# croc.net
KiCad netlist of a schematic drawn in EAGLE
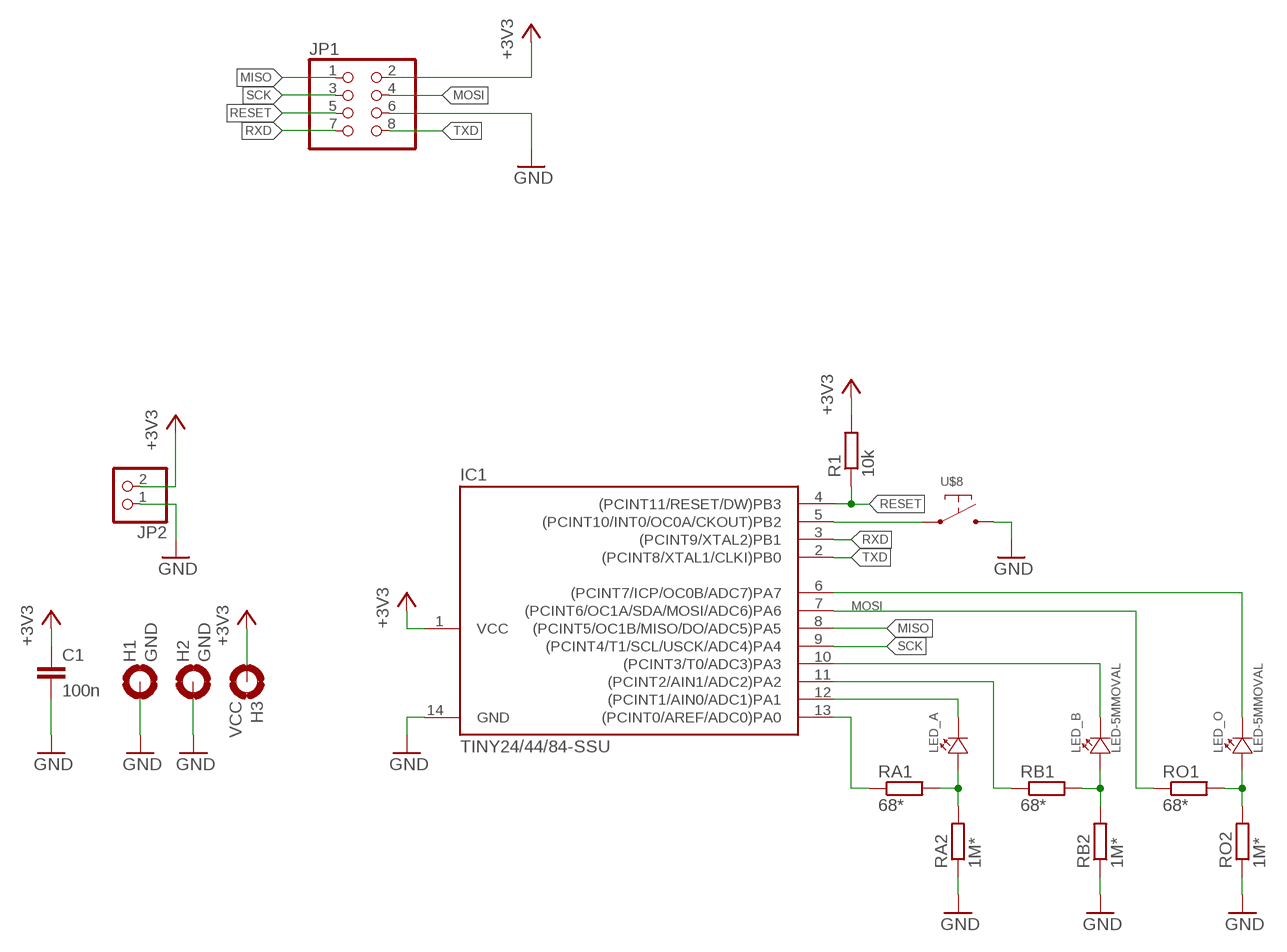
[diagram p0: schematic, sheet 1]

(export (version "E")
  (design (tool "Eeschema 10.0.6"))
  (components
    (comp (ref "C1")
      (value "100n")
      (footprint "eagle-import:C0603")
      (libsource (lib "eagle-import") (part "C-EUC0603"))
    )
    (comp (ref "H1")
      (value "GND")
      (footprint "eagle-import:3,0-PAD")
      (libsource (lib "eagle-import") (part "MOUNT-PAD-ROUND3.0"))
    )
    (comp (ref "H2")
      (value "GND")
      (footprint "eagle-import:3,0-PAD")
      (libsource (lib "eagle-import") (part "MOUNT-PAD-ROUND3.0"))
    )
    (comp (ref "H3")
      (value "VCC")
      (footprint "eagle-import:3,0-PAD")
      (libsource (lib "eagle-import") (part "MOUNT-PAD-ROUND3.0"))
    )
    (comp (ref "IC1")
      (value "TINY24/44/84-SSU")
      (footprint "eagle-import:SOIC14")
      (libsource (lib "eagle-import") (part "TINY24/44/84-SSU"))
    )
    (comp (ref "JP1")
      (value "PINHD-2X4/EDGE")
      (footprint "eagle-import:2X04_EDGE")
      (libsource (lib "eagle-import") (part "PINHD-2X4/EDGE"))
    )
    (comp (ref "JP2")
      (value "PINHD-1X2")
      (footprint "eagle-import:1X02")
      (libsource (lib "eagle-import") (part "PINHD-1X2"))
    )
    (comp (ref "LED_A")
      (value "LED-5MMOVAL")
      (footprint "eagle-import:LED-5MM-EDGE-OVAL")
      (libsource (lib "eagle-import") (part "LED-5MMOVAL"))
    )
    (comp (ref "LED_B")
      (value "LED-5MMOVAL")
      (footprint "eagle-import:LED-5MM-EDGE-OVAL")
      (libsource (lib "eagle-import") (part "LED-5MMOVAL"))
    )
    (comp (ref "LED_O")
      (value "LED-5MMOVAL")
      (footprint "eagle-import:LED-5MM-EDGE-OVAL")
      (libsource (lib "eagle-import") (part "LED-5MMOVAL"))
    )
    (comp (ref "R1")
      (value "10k")
      (footprint "eagle-import:R0603")
      (libsource (lib "eagle-import") (part "R-EU_R0603"))
    )
    (comp (ref "RA1")
      (value "68*")
      (footprint "eagle-import:R0603")
      (libsource (lib "eagle-import") (part "R-EU_R0603"))
    )
    (comp (ref "RA2")
      (value "1M*")
      (footprint "eagle-import:R0603")
      (libsource (lib "eagle-import") (part "R-EU_R0603"))
    )
    (comp (ref "RB1")
      (value "68*")
      (footprint "eagle-import:R0603")
      (libsource (lib "eagle-import") (part "R-EU_R0603"))
    )
    (comp (ref "RB2")
      (value "1M*")
      (footprint "eagle-import:R0603")
      (libsource (lib "eagle-import") (part "R-EU_R0603"))
    )
    (comp (ref "RO1")
      (value "68*")
      (footprint "eagle-import:R0603")
      (libsource (lib "eagle-import") (part "R-EU_R0603"))
    )
    (comp (ref "RO2")
      (value "1M*")
      (footprint "eagle-import:R0603")
      (libsource (lib "eagle-import") (part "R-EU_R0603"))
    )
    (comp (ref "U$8")
      (value "SWITCH-DEFAULT_OFF-NO_SILK")
      (footprint "eagle-import:SWITCH-GENERIC-4_PIN-NO_SILK")
      (libsource (lib "eagle-import") (part "SWITCH-DEFAULT_OFF-NO_SILK"))
    )
  )
  (nets
    (net (code "1") (name "+3V3") (class "Default")
      (node (ref "C1") (pin "1") (pinfunction "1_1") (pintype "passive"))
      (node (ref "H3") (pin "B3,0") (pinfunction "MOUNT_B3,0") (pintype "passive"))
      (node (ref "IC1") (pin "1") (pinfunction "VCC_1") (pintype "power_in"))
      (node (ref "JP1") (pin "2") (pinfunction "2_2") (pintype "passive"))
      (node (ref "JP2") (pin "2") (pinfunction "2_2") (pintype "passive"))
      (node (ref "R1") (pin "2") (pinfunction "2_2") (pintype "passive"))
    )
    (net (code "2") (name "GND") (class "Default")
      (node (ref "C1") (pin "2") (pinfunction "2_2") (pintype "passive"))
      (node (ref "H1") (pin "B3,0") (pinfunction "MOUNT_B3,0") (pintype "passive"))
      (node (ref "H2") (pin "B3,0") (pinfunction "MOUNT_B3,0") (pintype "passive"))
      (node (ref "IC1") (pin "14") (pinfunction "GND_14") (pintype "power_in"))
      (node (ref "JP1") (pin "6") (pinfunction "6_6") (pintype "passive"))
      (node (ref "JP2") (pin "1") (pinfunction "1_1") (pintype "passive"))
      (node (ref "RA2") (pin "1") (pinfunction "1_1") (pintype "passive"))
      (node (ref "RB2") (pin "1") (pinfunction "1_1") (pintype "passive"))
      (node (ref "RO2") (pin "1") (pinfunction "1_1") (pintype "passive"))
      (node (ref "U$8") (pin "P$3") (pinfunction "P$2_P$3") (pintype "bidirectional"))
      (node (ref "U$8") (pin "P$4") (pinfunction "P$2_P$4") (pintype "bidirectional"))
    )
    (net (code "3") (name "MISO") (class "Default")
      (node (ref "IC1") (pin "8") (pinfunction "(PCINT5/OC1B/MISO/DO/ADC5)PA5_8") (pintype "bidirectional"))
      (node (ref "JP1") (pin "1") (pinfunction "1_1") (pintype "passive"))
    )
    (net (code "4") (name "MOSI") (class "Default")
      (node (ref "IC1") (pin "7") (pinfunction "(PCINT6/OC1A/SDA/MOSI/ADC6)PA6_7") (pintype "bidirectional"))
      (node (ref "JP1") (pin "4") (pinfunction "4_4") (pintype "passive"))
      (node (ref "RO1") (pin "1") (pinfunction "1_1") (pintype "passive"))
    )
    (net (code "5") (name "Net-(IC1-(PCINT0{slash}AREF{slash}ADC0)PA0)") (class "Default")
      (node (ref "IC1") (pin "13") (pinfunction "(PCINT0/AREF/ADC0)PA0_13") (pintype "bidirectional"))
      (node (ref "RA1") (pin "1") (pinfunction "1_1") (pintype "passive"))
    )
    (net (code "6") (name "Net-(IC1-(PCINT1{slash}AIN0{slash}ADC1)PA1)") (class "Default")
      (node (ref "IC1") (pin "12") (pinfunction "(PCINT1/AIN0/ADC1)PA1_12") (pintype "bidirectional"))
      (node (ref "LED_A") (pin "K") (pinfunction "C_K") (pintype "bidirectional"))
    )
    (net (code "7") (name "Net-(IC1-(PCINT2{slash}AIN1{slash}ADC2)PA2)") (class "Default")
      (node (ref "IC1") (pin "11") (pinfunction "(PCINT2/AIN1/ADC2)PA2_11") (pintype "bidirectional"))
      (node (ref "RB1") (pin "1") (pinfunction "1_1") (pintype "passive"))
    )
    (net (code "8") (name "Net-(IC1-(PCINT3{slash}T0{slash}ADC3)PA3)") (class "Default")
      (node (ref "IC1") (pin "10") (pinfunction "(PCINT3/T0/ADC3)PA3_10") (pintype "bidirectional"))
      (node (ref "LED_B") (pin "K") (pinfunction "C_K") (pintype "bidirectional"))
    )
    (net (code "9") (name "Net-(IC1-(PCINT7{slash}ICP{slash}OC0B{slash}ADC7)PA7)") (class "Default")
      (node (ref "IC1") (pin "6") (pinfunction "(PCINT7/ICP/OC0B/ADC7)PA7_6") (pintype "bidirectional"))
      (node (ref "LED_O") (pin "K") (pinfunction "C_K") (pintype "bidirectional"))
    )
    (net (code "10") (name "Net-(IC1-(PCINT10{slash}INT0{slash}OC0A{slash}CKOUT)PB2)") (class "Default")
      (node (ref "IC1") (pin "5") (pinfunction "(PCINT10/INT0/OC0A/CKOUT)PB2_5") (pintype "bidirectional"))
      (node (ref "U$8") (pin "P$1") (pinfunction "P$1_P$1") (pintype "bidirectional"))
      (node (ref "U$8") (pin "P$2") (pinfunction "P$1_P$2") (pintype "bidirectional"))
    )
    (net (code "11") (name "Net-(LED_A-PadA)") (class "Default")
      (node (ref "LED_A") (pin "A") (pinfunction "A_A") (pintype "bidirectional"))
      (node (ref "RA1") (pin "2") (pinfunction "2_2") (pintype "passive"))
      (node (ref "RA2") (pin "2") (pinfunction "2_2") (pintype "passive"))
    )
    (net (code "12") (name "Net-(LED_B-PadA)") (class "Default")
      (node (ref "LED_B") (pin "A") (pinfunction "A_A") (pintype "bidirectional"))
      (node (ref "RB1") (pin "2") (pinfunction "2_2") (pintype "passive"))
      (node (ref "RB2") (pin "2") (pinfunction "2_2") (pintype "passive"))
    )
    (net (code "13") (name "Net-(LED_O-PadA)") (class "Default")
      (node (ref "LED_O") (pin "A") (pinfunction "A_A") (pintype "bidirectional"))
      (node (ref "RO1") (pin "2") (pinfunction "2_2") (pintype "passive"))
      (node (ref "RO2") (pin "2") (pinfunction "2_2") (pintype "passive"))
    )
    (net (code "14") (name "RESET") (class "Default")
      (node (ref "IC1") (pin "4") (pinfunction "(PCINT11/RESET/DW)PB3_4") (pintype "bidirectional"))
      (node (ref "JP1") (pin "5") (pinfunction "5_5") (pintype "passive"))
      (node (ref "R1") (pin "1") (pinfunction "1_1") (pintype "passive"))
    )
    (net (code "15") (name "RXD") (class "Default")
      (node (ref "IC1") (pin "3") (pinfunction "(PCINT9/XTAL2)PB1_3") (pintype "bidirectional"))
      (node (ref "JP1") (pin "7") (pinfunction "7_7") (pintype "passive"))
    )
    (net (code "16") (name "SCK") (class "Default")
      (node (ref "IC1") (pin "9") (pinfunction "(PCINT4/T1/SCL/USCK/ADC4)PA4_9") (pintype "bidirectional"))
      (node (ref "JP1") (pin "3") (pinfunction "3_3") (pintype "passive"))
    )
    (net (code "17") (name "TXD") (class "Default")
      (node (ref "IC1") (pin "2") (pinfunction "(PCINT8/XTAL1/CLKI)PB0_2") (pintype "bidirectional"))
      (node (ref "JP1") (pin "8") (pinfunction "8_8") (pintype "passive"))
    )
  )
)
